# esp_board2.net
KiCad netlist of a schematic drawn in EAGLE
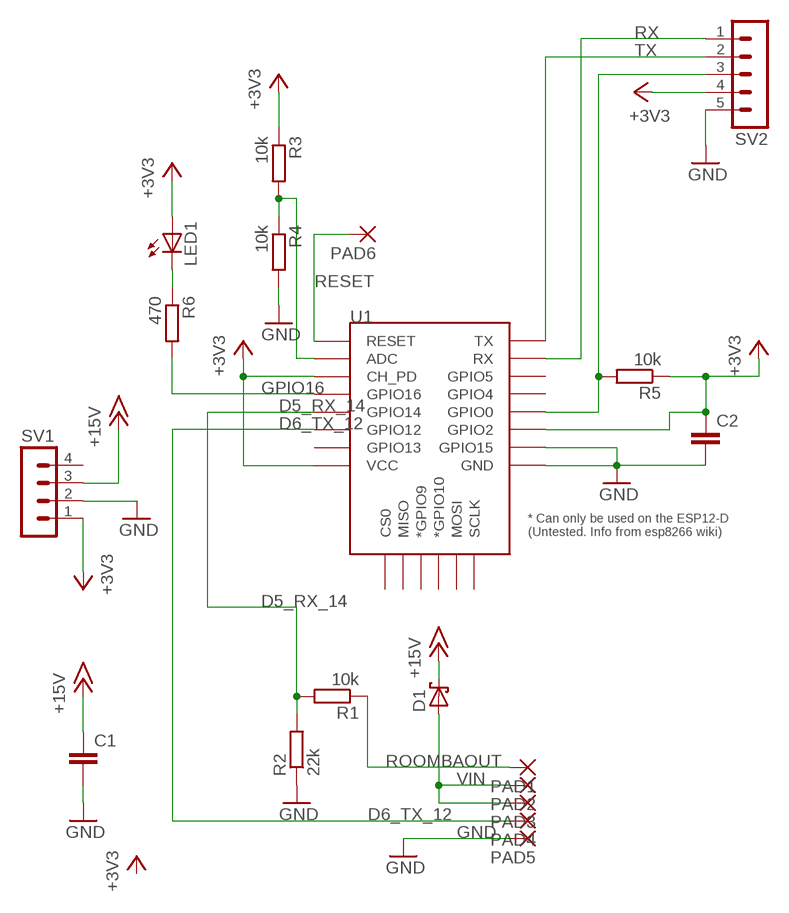
[diagram p0: schematic, sheet 1]

(export (version "E")
  (design (tool "Eeschema 10.0.6"))
  (components
    (comp (ref "C1")
      (value "C-EUC3225")
      (footprint "eagle-import:C3225")
      (libsource (lib "eagle-import") (part "C-EUC3225"))
    )
    (comp (ref "C2")
      (value "C-EUC3225")
      (footprint "eagle-import:C3225")
      (libsource (lib "eagle-import") (part "C-EUC3225"))
    )
    (comp (ref "D1")
      (value "SCHOTTKY-DIODESMC")
      (footprint "eagle-import:SMC")
      (libsource (lib "eagle-import") (part "SCHOTTKY-DIODESMC"))
    )
    (comp (ref "LED1")
      (value "LEDCHIP-LED0805")
      (footprint "eagle-import:CHIP-LED0805")
      (libsource (lib "eagle-import") (part "LEDCHIP-LED0805"))
    )
    (comp (ref "PAD1")
      (value "1,6/0,8")
      (footprint "eagle-import:1,6_0,8")
      (libsource (lib "eagle-import") (part "1,6/0,8"))
    )
    (comp (ref "PAD2")
      (value "1,6/0,8")
      (footprint "eagle-import:1,6_0,8")
      (libsource (lib "eagle-import") (part "1,6/0,8"))
    )
    (comp (ref "PAD3")
      (value "1,6/0,8")
      (footprint "eagle-import:1,6_0,8")
      (libsource (lib "eagle-import") (part "1,6/0,8"))
    )
    (comp (ref "PAD4")
      (value "1,6/0,8")
      (footprint "eagle-import:1,6_0,8")
      (libsource (lib "eagle-import") (part "1,6/0,8"))
    )
    (comp (ref "PAD5")
      (value "1,6/0,8")
      (footprint "eagle-import:1,6_0,8")
      (libsource (lib "eagle-import") (part "1,6/0,8"))
    )
    (comp (ref "PAD6")
      (value "SMD2")
      (footprint "eagle-import:SMD1,27-2,54")
      (libsource (lib "eagle-import") (part "SMD2"))
    )
    (comp (ref "R1")
      (value "10k")
      (footprint "eagle-import:R0805")
      (libsource (lib "eagle-import") (part "R-EU_R0805"))
    )
    (comp (ref "R2")
      (value "22k")
      (footprint "eagle-import:R0805")
      (libsource (lib "eagle-import") (part "R-EU_R0805"))
    )
    (comp (ref "R3")
      (value "10k")
      (footprint "eagle-import:R0805")
      (libsource (lib "eagle-import") (part "R-EU_R0805"))
    )
    (comp (ref "R4")
      (value "10k")
      (footprint "eagle-import:R0805")
      (libsource (lib "eagle-import") (part "R-EU_R0805"))
    )
    (comp (ref "R5")
      (value "10k")
      (footprint "eagle-import:R0805")
      (libsource (lib "eagle-import") (part "R-EU_R0805"))
    )
    (comp (ref "R6")
      (value "470")
      (footprint "eagle-import:R0805")
      (libsource (lib "eagle-import") (part "R-EU_R0805"))
    )
    (comp (ref "SV1")
      (value "MA04-1")
      (footprint "eagle-import:MA04-1")
      (libsource (lib "eagle-import") (part "MA04-1"))
    )
    (comp (ref "SV2")
      (value "MA05-1")
      (footprint "eagle-import:MA05-1")
      (libsource (lib "eagle-import") (part "MA05-1"))
    )
    (comp (ref "U1")
      (value "ESP12ESMD")
      (footprint "eagle-import:ESP12E-SMD")
      (libsource (lib "eagle-import") (part "ESP12ESMD"))
    )
  )
  (nets
    (net (code "1") (name "+3V3") (class "Default")
      (node (ref "C2") (pin "1") (pinfunction "1_1") (pintype "passive"))
      (node (ref "LED1") (pin "A") (pinfunction "A_A") (pintype "passive"))
      (node (ref "R3") (pin "1") (pinfunction "1_1") (pintype "passive"))
      (node (ref "R5") (pin "1") (pinfunction "1_1") (pintype "passive"))
      (node (ref "SV1") (pin "1") (pinfunction "1_1") (pintype "passive"))
      (node (ref "SV2") (pin "4") (pinfunction "4_4") (pintype "passive"))
      (node (ref "U1") (pin "CH_PD") (pinfunction "CH_PD_CH_PD") (pintype "bidirectional"))
      (node (ref "U1") (pin "GPIO2") (pinfunction "GPIO2_GPIO2") (pintype "bidirectional"))
      (node (ref "U1") (pin "VCC") (pinfunction "VCC_VCC") (pintype "bidirectional"))
    )
    (net (code "2") (name "+15V") (class "Default")
      (node (ref "C1") (pin "1") (pinfunction "1_1") (pintype "passive"))
      (node (ref "D1") (pin "C") (pinfunction "C_C") (pintype "passive"))
      (node (ref "SV1") (pin "3") (pinfunction "3_3") (pintype "passive"))
    )
    (net (code "3") (name "/D5_RX_14") (class "Default")
      (node (ref "R1") (pin "2") (pinfunction "2_2") (pintype "passive"))
      (node (ref "R2") (pin "2") (pinfunction "2_2") (pintype "passive"))
      (node (ref "U1") (pin "GPIO14") (pinfunction "GPIO14_GPIO14") (pintype "bidirectional"))
    )
    (net (code "4") (name "/D6_TX_12") (class "Default")
      (node (ref "PAD4") (pin "1") (pinfunction "P_1") (pintype "passive"))
      (node (ref "U1") (pin "GPIO12") (pinfunction "GPIO12_GPIO12") (pintype "bidirectional"))
    )
    (net (code "5") (name "/GPIO16") (class "Default")
      (node (ref "R6") (pin "2") (pinfunction "2_2") (pintype "passive"))
      (node (ref "U1") (pin "GPIO16") (pinfunction "GPIO16_GPIO16") (pintype "bidirectional"))
    )
    (net (code "6") (name "/RESET") (class "Default")
      (node (ref "PAD6") (pin "1") (pinfunction "P_1") (pintype "passive"))
      (node (ref "U1") (pin "RESET") (pinfunction "RESET_RESET") (pintype "bidirectional"))
    )
    (net (code "7") (name "/ROOMBAOUT") (class "Default")
      (node (ref "PAD1") (pin "1") (pinfunction "P_1") (pintype "passive"))
      (node (ref "R1") (pin "1") (pinfunction "1_1") (pintype "passive"))
    )
    (net (code "8") (name "/RX") (class "Default")
      (node (ref "SV2") (pin "1") (pinfunction "1_1") (pintype "passive"))
      (node (ref "U1") (pin "RXD0") (pinfunction "RX_RXD0") (pintype "bidirectional"))
    )
    (net (code "9") (name "/TX") (class "Default")
      (node (ref "SV2") (pin "2") (pinfunction "2_2") (pintype "passive"))
      (node (ref "U1") (pin "TXD0") (pinfunction "TX_TXD0") (pintype "bidirectional"))
    )
    (net (code "10") (name "/VIN") (class "Default")
      (node (ref "D1") (pin "A") (pinfunction "A_A") (pintype "passive"))
      (node (ref "PAD2") (pin "1") (pinfunction "P_1") (pintype "passive"))
      (node (ref "PAD3") (pin "1") (pinfunction "P_1") (pintype "passive"))
    )
    (net (code "11") (name "GND") (class "Default")
      (node (ref "C1") (pin "2") (pinfunction "2_2") (pintype "passive"))
      (node (ref "C2") (pin "2") (pinfunction "2_2") (pintype "passive"))
      (node (ref "PAD5") (pin "1") (pinfunction "P_1") (pintype "passive"))
      (node (ref "R2") (pin "1") (pinfunction "1_1") (pintype "passive"))
      (node (ref "R4") (pin "2") (pinfunction "2_2") (pintype "passive"))
      (node (ref "SV1") (pin "2") (pinfunction "2_2") (pintype "passive"))
      (node (ref "SV2") (pin "5") (pinfunction "5_5") (pintype "passive"))
      (node (ref "U1") (pin "GND") (pinfunction "GND_GND") (pintype "bidirectional"))
      (node (ref "U1") (pin "GPIO15") (pinfunction "GPIO15_GPIO15") (pintype "bidirectional"))
    )
    (net (code "12") (name "Net-(LED1-PadC)") (class "Default")
      (node (ref "LED1") (pin "C") (pinfunction "C_C") (pintype "passive"))
      (node (ref "R6") (pin "1") (pinfunction "1_1") (pintype "passive"))
    )
    (net (code "13") (name "Net-(R3-Pad2)") (class "Default")
      (node (ref "R3") (pin "2") (pinfunction "2_2") (pintype "passive"))
      (node (ref "R4") (pin "1") (pinfunction "1_1") (pintype "passive"))
      (node (ref "U1") (pin "ADC") (pinfunction "ADC_ADC") (pintype "bidirectional"))
    )
    (net (code "14") (name "Net-(R5-Pad2)") (class "Default")
      (node (ref "R5") (pin "2") (pinfunction "2_2") (pintype "passive"))
      (node (ref "SV2") (pin "3") (pinfunction "3_3") (pintype "passive"))
      (node (ref "U1") (pin "GPIO0") (pinfunction "GPIO0_GPIO0") (pintype "bidirectional"))
    )
    (net (code "15") (name "unconnected-(SV1-Pad4)") (class "Default")
      (node (ref "SV1") (pin "4") (pinfunction "4_4") (pintype "passive"))
    )
    (net (code "16") (name "unconnected-(U1-*GPIO9-PadGPIO9)") (class "Default")
      (node (ref "U1") (pin "GPIO9") (pinfunction "*GPIO9_GPIO9") (pintype "bidirectional"))
    )
    (net (code "17") (name "unconnected-(U1-*GPIO10-PadGPIO10)") (class "Default")
      (node (ref "U1") (pin "GPIO10") (pinfunction "*GPIO10_GPIO10") (pintype "bidirectional"))
    )
    (net (code "18") (name "unconnected-(U1-PadCS0)") (class "Default")
      (node (ref "U1") (pin "CS0") (pinfunction "CS0_CS0") (pintype "bidirectional"))
    )
    (net (code "19") (name "unconnected-(U1-PadGPIO4)") (class "Default")
      (node (ref "U1") (pin "GPIO4") (pinfunction "GPIO4_GPIO4") (pintype "bidirectional"))
    )
    (net (code "20") (name "unconnected-(U1-PadGPIO5)") (class "Default")
      (node (ref "U1") (pin "GPIO5") (pinfunction "GPIO5_GPIO5") (pintype "bidirectional"))
    )
    (net (code "21") (name "unconnected-(U1-PadGPIO13)") (class "Default")
      (node (ref "U1") (pin "GPIO13") (pinfunction "GPIO13_GPIO13") (pintype "bidirectional"))
    )
    (net (code "22") (name "unconnected-(U1-PadMISO)") (class "Default")
      (node (ref "U1") (pin "MISO") (pinfunction "MISO_MISO") (pintype "bidirectional"))
    )
    (net (code "23") (name "unconnected-(U1-PadMOSI)") (class "Default")
      (node (ref "U1") (pin "MOSI") (pinfunction "MOSI_MOSI") (pintype "bidirectional"))
    )
    (net (code "24") (name "unconnected-(U1-PadSCLK)") (class "Default")
      (node (ref "U1") (pin "SCLK") (pinfunction "SCLK_SCLK") (pintype "bidirectional"))
    )
  )
)
